# STM32F334R8T6-Module.net
KiCad netlist of a schematic drawn in Altium Designer
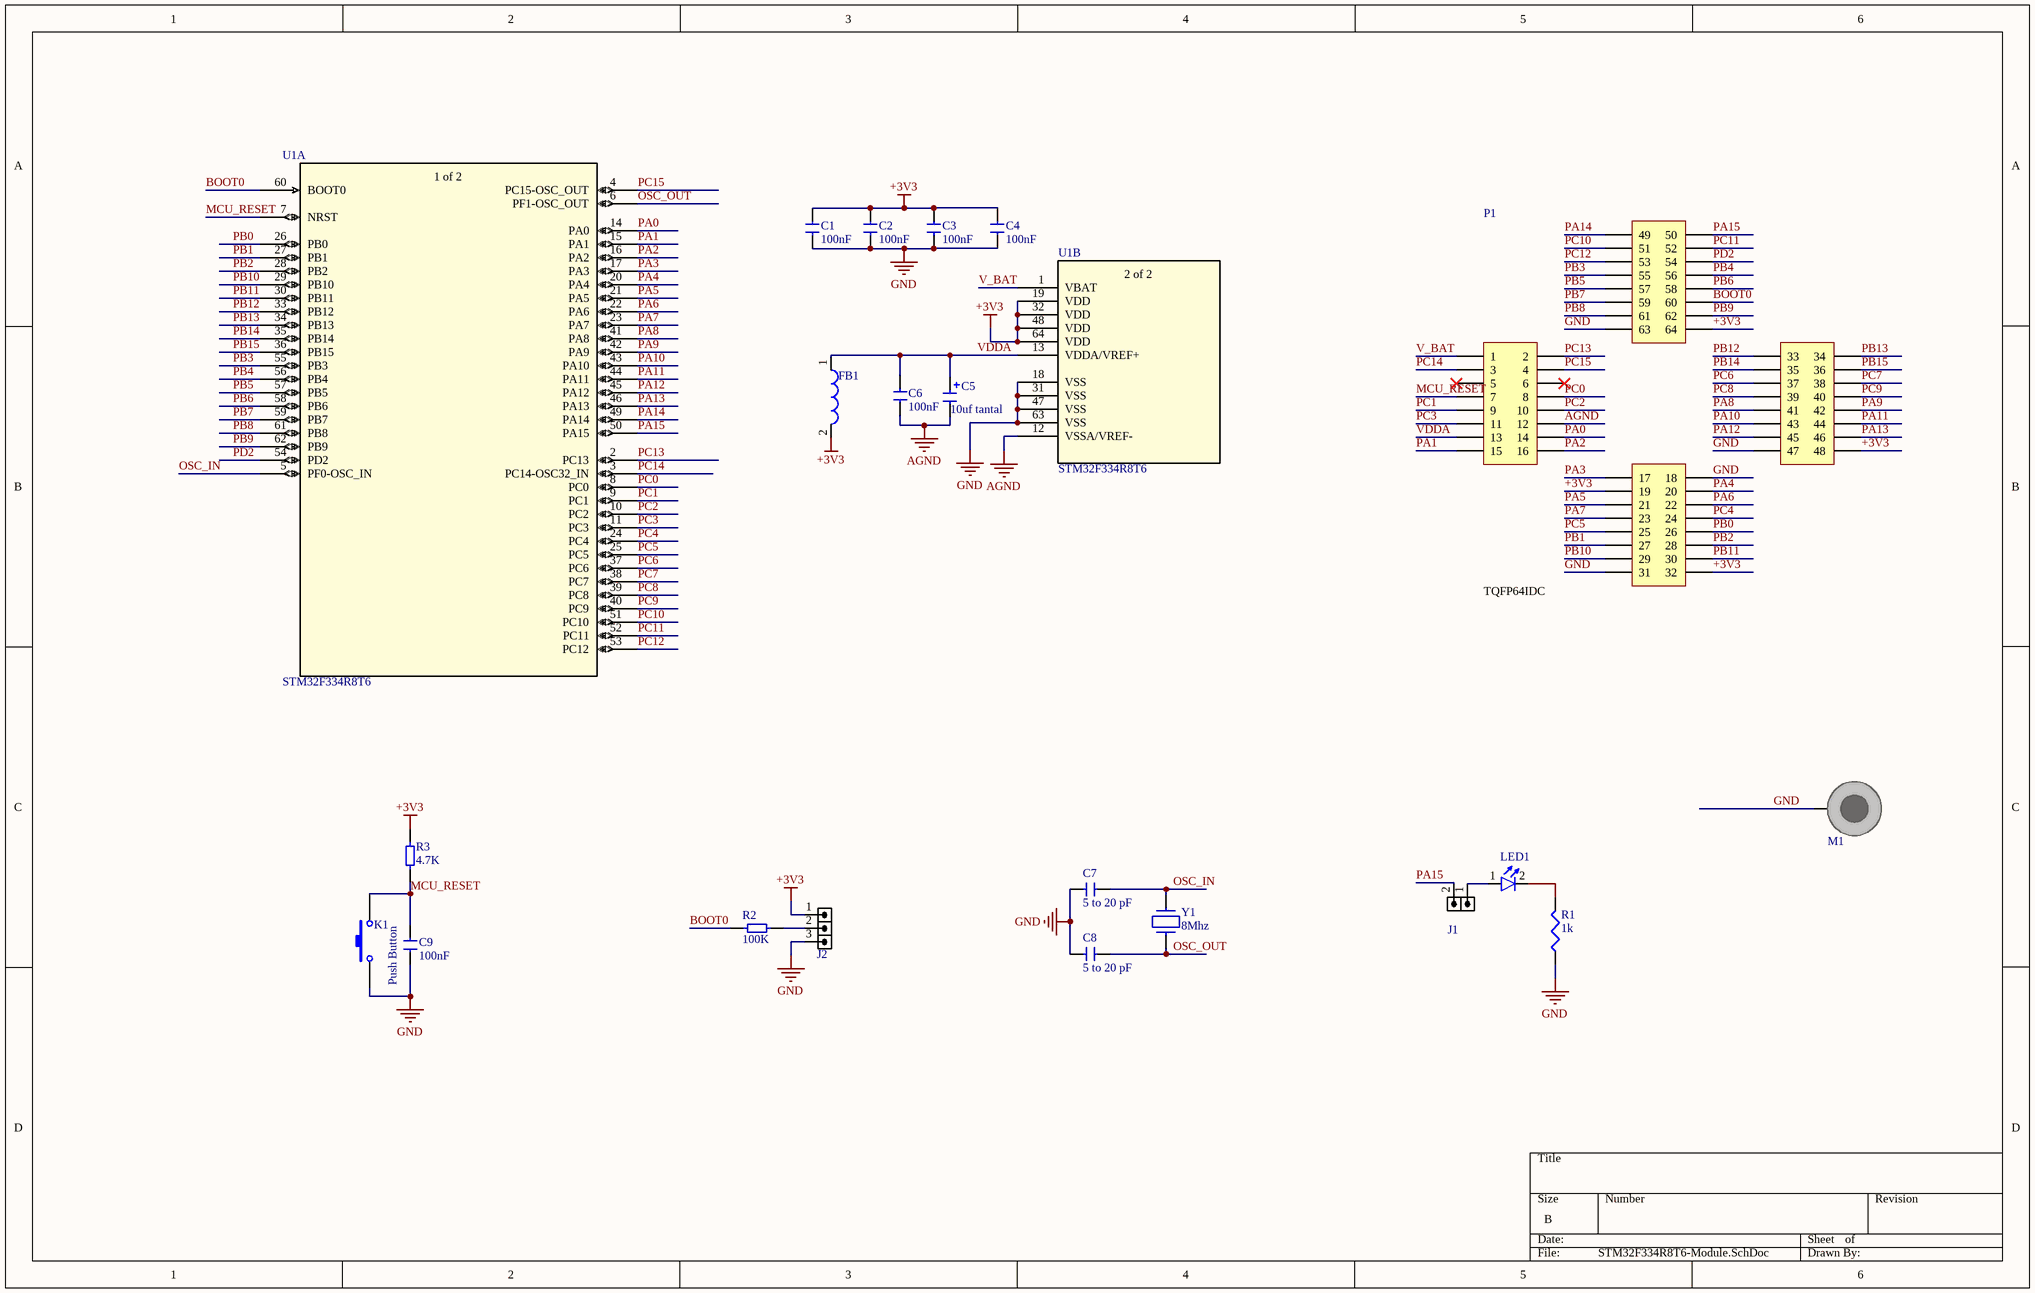
[diagram p0: STM32F334R8T6-Module.SchDoc]

(export (version "E")
  (design (tool "Eeschema 10.0.6"))
  (components
    (comp (ref "C1")
      (value "Comment")
      (footprint "CAP 1206 (3216X15L)")
      (fields (field (name "ALTIUM_UNNAMED_1") "100nF"))
      (libsource (lib "DotexGroup_LIB") (part "Capacitor SMD"))
    )
    (comp (ref "C2")
      (value "Comment")
      (footprint "CAP 1206 (3216X15L)")
      (fields (field (name "ALTIUM_UNNAMED_1") "100nF"))
      (libsource (lib "DotexGroup_LIB") (part "Capacitor SMD"))
    )
    (comp (ref "C3")
      (value "Comment")
      (footprint "CAP 1206 (3216X15L)")
      (fields (field (name "ALTIUM_UNNAMED_1") "100nF"))
      (libsource (lib "DotexGroup_LIB") (part "Capacitor SMD"))
    )
    (comp (ref "C4")
      (value "Comment")
      (footprint "CAP 1206 (3216X15L)")
      (fields (field (name "ALTIUM_UNNAMED_1") "100nF"))
      (libsource (lib "DotexGroup_LIB") (part "Capacitor SMD"))
    )
    (comp (ref "C5")
      (value "10uf tantal")
      (footprint "cap-e-2")
      (libsource (lib "DotexGroup_LIB") (part "Capacitor Tantalium"))
    )
    (comp (ref "C6")
      (value "Comment")
      (footprint "CAP 1206 (3216X15L)")
      (fields (field (name "ALTIUM_UNNAMED_1") "100nF"))
      (libsource (lib "DotexGroup_LIB") (part "Capacitor SMD"))
    )
    (comp (ref "C7")
      (value "Comment")
      (footprint "CAP 1206 (3216X15L)")
      (fields (field (name "ALTIUM_UNNAMED_1") "5 to 20 pF"))
      (libsource (lib "DotexGroup_LIB") (part "Capacitor SMD"))
    )
    (comp (ref "C8")
      (value "Comment")
      (footprint "CAP 1206 (3216X15L)")
      (fields (field (name "ALTIUM_UNNAMED_1") "5 to 20 pF"))
      (libsource (lib "DotexGroup_LIB") (part "Capacitor SMD"))
    )
    (comp (ref "C9")
      (value "Comment")
      (footprint "CAP 1206 (3216X15L)")
      (fields (field (name "ALTIUM_UNNAMED_1") "100nF"))
      (libsource (lib "DotexGroup_LIB") (part "Capacitor SMD"))
    )
    (comp (ref "FB1")
      (value "Comment")
      (footprint "INDC4532")
      (libsource (lib "DotexGroup_LIB") (part "Ferrit Bead"))
    )
    (comp (ref "J1")
      (value "HDRM2")
      (footprint "HDR1X2")
      (description "CONN, HEADER, Male, pitch: 2.54mm, 2POS")
      (libsource (lib "conn_header") (part "HDR_M_1X2"))
    )
    (comp (ref "J2")
      (value "HDRM3")
      (footprint "HDR1X3")
      (description "CONN, HEADER, Male, pitch: 2.54mm, 3POS")
      (libsource (lib "conn_header") (part "HDR_M_1X3"))
    )
    (comp (ref "K1")
      (value "Push Button")
      (footprint "SW PB SMD")
      (libsource (lib "DotexGroup_LIB") (part "Push Kay"))
    )
    (comp (ref "LED1")
      (value "HB")
      (footprint "LED SMD 1206")
      (description "LED")
      (fields (field (name "DESIGNER") "Saeid Jorablo"))
      (libsource (lib "3D") (part "LED"))
    )
    (comp (ref "M1")
      (value "Comment")
      (footprint "Stud-hole")
      (description "SCREW mouting, M1.6, 1.6mm diameter and 3.2mm PanHead")
      (libsource (lib "DotexGroup_LIB") (part "SCMH_M1P6"))
    )
    (comp (ref "P1")
      (value "TQFP64IDC")
      (footprint "tqfp64idc")
      (libsource (lib "Mylibrary2019") (part "TQFP64IDC"))
    )
    (comp (ref "R1") (value "1k") (footprint "RES 1206 (3216X08L)") (libsource (lib "*") (part "R")))
    (comp (ref "R2")
      (value "Comment")
      (footprint "RES 1206 (3216X08L)")
      (fields (field (name "ALTIUM_UNNAMED_1") "100K"))
      (libsource (lib "DotexGroup_LIB") (part "Resistor SMD"))
    )
    (comp (ref "R3")
      (value "Comment")
      (footprint "RES 1206 (3216X08L)")
      (fields (field (name "ALTIUM_UNNAMED_1") "4.7K"))
      (libsource (lib "DotexGroup_LIB") (part "Resistor SMD"))
    )
    (comp (ref "U1")
      (value "STM32F334R8T6")
      (footprint "STM32F334R8T6")
      (description "No Description Available")
      (fields (field (name "COPYRIGHT") "Copyright (C) 2023 Ultra Librarian. All rights reserved."))
      (libsource (lib "STM32F334R8T6") (part "STM32F334R8T6"))
    )
    (comp (ref "Y1")
      (value "8Mhz")
      (footprint "Crystal SMD")
      (libsource (lib "DotexGroup_LIB") (part "Xtal"))
    )
  )
  (nets
    (net (code "1") (name "+3V3") (class "Default")
      (node (ref "C1") (pin "2") (pintype "passive"))
      (node (ref "C2") (pin "2") (pintype "passive"))
      (node (ref "C3") (pin "2") (pintype "passive"))
      (node (ref "C4") (pin "2") (pintype "passive"))
      (node (ref "FB1") (pin "2") (pinfunction "2_2") (pintype "passive"))
      (node (ref "J2") (pin "1") (pinfunction "1_1") (pintype "passive"))
      (node (ref "P1") (pin "19") (pinfunction "19_19") (pintype "passive"))
      (node (ref "P1") (pin "32") (pinfunction "32_32") (pintype "passive"))
      (node (ref "P1") (pin "48") (pinfunction "48_48") (pintype "passive"))
      (node (ref "P1") (pin "64") (pinfunction "64_64") (pintype "passive"))
      (node (ref "R3") (pin "1") (pintype "passive"))
      (node (ref "U1") (pin "19") (pinfunction "VDD_19") (pintype "power_in"))
      (node (ref "U1") (pin "32") (pinfunction "VDD_32") (pintype "power_in"))
      (node (ref "U1") (pin "48") (pinfunction "VDD_48") (pintype "power_in"))
      (node (ref "U1") (pin "64") (pinfunction "VDD_64") (pintype "power_in"))
    )
    (net (code "2") (name "/BOOT0") (class "Default")
      (node (ref "P1") (pin "60") (pinfunction "60_60") (pintype "passive"))
      (node (ref "R2") (pin "1") (pintype "passive"))
      (node (ref "U1") (pin "60") (pinfunction "BOOT0_60") (pintype "input"))
    )
    (net (code "3") (name "/MCU_RESET") (class "Default")
      (node (ref "C9") (pin "1") (pintype "passive"))
      (node (ref "K1") (pin "2") (pinfunction "2_2") (pintype "passive"))
      (node (ref "P1") (pin "7") (pinfunction "7_7") (pintype "passive"))
      (node (ref "R3") (pin "2") (pintype "passive"))
      (node (ref "U1") (pin "7") (pinfunction "NRST_7") (pintype "bidirectional"))
    )
    (net (code "4") (name "/OSC_IN") (class "Default")
      (node (ref "C7") (pin "2") (pintype "passive"))
      (node (ref "U1") (pin "5") (pinfunction "PF0-OSC_IN_5") (pintype "bidirectional"))
      (node (ref "Y1") (pin "2") (pintype "passive"))
    )
    (net (code "5") (name "/OSC_OUT") (class "Default")
      (node (ref "C8") (pin "1") (pintype "passive"))
      (node (ref "U1") (pin "6") (pinfunction "PF1-OSC_OUT_6") (pintype "bidirectional"))
      (node (ref "Y1") (pin "1") (pintype "passive"))
    )
    (net (code "6") (name "/PA0") (class "Default")
      (node (ref "P1") (pin "14") (pinfunction "14_14") (pintype "passive"))
      (node (ref "U1") (pin "14") (pinfunction "PA0_14") (pintype "bidirectional"))
    )
    (net (code "7") (name "/PA1") (class "Default")
      (node (ref "P1") (pin "15") (pinfunction "15_15") (pintype "passive"))
      (node (ref "U1") (pin "15") (pinfunction "PA1_15") (pintype "bidirectional"))
    )
    (net (code "8") (name "/PA2") (class "Default")
      (node (ref "P1") (pin "16") (pinfunction "16_16") (pintype "passive"))
      (node (ref "U1") (pin "16") (pinfunction "PA2_16") (pintype "bidirectional"))
    )
    (net (code "9") (name "/PA3") (class "Default")
      (node (ref "P1") (pin "17") (pinfunction "17_17") (pintype "passive"))
      (node (ref "U1") (pin "17") (pinfunction "PA3_17") (pintype "bidirectional"))
    )
    (net (code "10") (name "/PA4") (class "Default")
      (node (ref "P1") (pin "20") (pinfunction "20_20") (pintype "passive"))
      (node (ref "U1") (pin "20") (pinfunction "PA4_20") (pintype "bidirectional"))
    )
    (net (code "11") (name "/PA5") (class "Default")
      (node (ref "P1") (pin "21") (pinfunction "21_21") (pintype "passive"))
      (node (ref "U1") (pin "21") (pinfunction "PA5_21") (pintype "bidirectional"))
    )
    (net (code "12") (name "/PA6") (class "Default")
      (node (ref "P1") (pin "22") (pinfunction "22_22") (pintype "passive"))
      (node (ref "U1") (pin "22") (pinfunction "PA6_22") (pintype "bidirectional"))
    )
    (net (code "13") (name "/PA7") (class "Default")
      (node (ref "P1") (pin "23") (pinfunction "23_23") (pintype "passive"))
      (node (ref "U1") (pin "23") (pinfunction "PA7_23") (pintype "bidirectional"))
    )
    (net (code "14") (name "/PA8") (class "Default")
      (node (ref "P1") (pin "41") (pinfunction "41_41") (pintype "passive"))
      (node (ref "U1") (pin "41") (pinfunction "PA8_41") (pintype "bidirectional"))
    )
    (net (code "15") (name "/PA9") (class "Default")
      (node (ref "P1") (pin "42") (pinfunction "42_42") (pintype "passive"))
      (node (ref "U1") (pin "42") (pinfunction "PA9_42") (pintype "bidirectional"))
    )
    (net (code "16") (name "/PA10") (class "Default")
      (node (ref "P1") (pin "43") (pinfunction "43_43") (pintype "passive"))
      (node (ref "U1") (pin "43") (pinfunction "PA10_43") (pintype "bidirectional"))
    )
    (net (code "17") (name "/PA11") (class "Default")
      (node (ref "P1") (pin "44") (pinfunction "44_44") (pintype "passive"))
      (node (ref "U1") (pin "44") (pinfunction "PA11_44") (pintype "bidirectional"))
    )
    (net (code "18") (name "/PA12") (class "Default")
      (node (ref "P1") (pin "45") (pinfunction "45_45") (pintype "passive"))
      (node (ref "U1") (pin "45") (pinfunction "PA12_45") (pintype "bidirectional"))
    )
    (net (code "19") (name "/PA13") (class "Default")
      (node (ref "P1") (pin "46") (pinfunction "46_46") (pintype "passive"))
      (node (ref "U1") (pin "46") (pinfunction "PA13_46") (pintype "bidirectional"))
    )
    (net (code "20") (name "/PA14") (class "Default")
      (node (ref "P1") (pin "49") (pinfunction "49_49") (pintype "passive"))
      (node (ref "U1") (pin "49") (pinfunction "PA14_49") (pintype "bidirectional"))
    )
    (net (code "21") (name "/PA15") (class "Default")
      (node (ref "J1") (pin "2") (pinfunction "2_2") (pintype "passive"))
      (node (ref "P1") (pin "50") (pinfunction "50_50") (pintype "passive"))
      (node (ref "U1") (pin "50") (pinfunction "PA15_50") (pintype "bidirectional"))
    )
    (net (code "22") (name "/PB0") (class "Default")
      (node (ref "P1") (pin "26") (pinfunction "26_26") (pintype "passive"))
      (node (ref "U1") (pin "26") (pinfunction "PB0_26") (pintype "bidirectional"))
    )
    (net (code "23") (name "/PB1") (class "Default")
      (node (ref "P1") (pin "27") (pinfunction "27_27") (pintype "passive"))
      (node (ref "U1") (pin "27") (pinfunction "PB1_27") (pintype "bidirectional"))
    )
    (net (code "24") (name "/PB2") (class "Default")
      (node (ref "P1") (pin "28") (pinfunction "28_28") (pintype "passive"))
      (node (ref "U1") (pin "28") (pinfunction "PB2_28") (pintype "bidirectional"))
    )
    (net (code "25") (name "/PB3") (class "Default")
      (node (ref "P1") (pin "55") (pinfunction "55_55") (pintype "passive"))
      (node (ref "U1") (pin "55") (pinfunction "PB3_55") (pintype "bidirectional"))
    )
    (net (code "26") (name "/PB4") (class "Default")
      (node (ref "P1") (pin "56") (pinfunction "56_56") (pintype "passive"))
      (node (ref "U1") (pin "56") (pinfunction "PB4_56") (pintype "bidirectional"))
    )
    (net (code "27") (name "/PB5") (class "Default")
      (node (ref "P1") (pin "57") (pinfunction "57_57") (pintype "passive"))
      (node (ref "U1") (pin "57") (pinfunction "PB5_57") (pintype "bidirectional"))
    )
    (net (code "28") (name "/PB6") (class "Default")
      (node (ref "P1") (pin "58") (pinfunction "58_58") (pintype "passive"))
      (node (ref "U1") (pin "58") (pinfunction "PB6_58") (pintype "bidirectional"))
    )
    (net (code "29") (name "/PB7") (class "Default")
      (node (ref "P1") (pin "59") (pinfunction "59_59") (pintype "passive"))
      (node (ref "U1") (pin "59") (pinfunction "PB7_59") (pintype "bidirectional"))
    )
    (net (code "30") (name "/PB8") (class "Default")
      (node (ref "P1") (pin "61") (pinfunction "61_61") (pintype "passive"))
      (node (ref "U1") (pin "61") (pinfunction "PB8_61") (pintype "bidirectional"))
    )
    (net (code "31") (name "/PB9") (class "Default")
      (node (ref "P1") (pin "62") (pinfunction "62_62") (pintype "passive"))
      (node (ref "U1") (pin "62") (pinfunction "PB9_62") (pintype "bidirectional"))
    )
    (net (code "32") (name "/PB10") (class "Default")
      (node (ref "P1") (pin "29") (pinfunction "29_29") (pintype "passive"))
      (node (ref "U1") (pin "29") (pinfunction "PB10_29") (pintype "bidirectional"))
    )
    (net (code "33") (name "/PB11") (class "Default")
      (node (ref "P1") (pin "30") (pinfunction "30_30") (pintype "passive"))
      (node (ref "U1") (pin "30") (pinfunction "PB11_30") (pintype "bidirectional"))
    )
    (net (code "34") (name "/PB12") (class "Default")
      (node (ref "P1") (pin "33") (pinfunction "33_33") (pintype "passive"))
      (node (ref "U1") (pin "33") (pinfunction "PB12_33") (pintype "bidirectional"))
    )
    (net (code "35") (name "/PB13") (class "Default")
      (node (ref "P1") (pin "34") (pinfunction "34_34") (pintype "passive"))
      (node (ref "U1") (pin "34") (pinfunction "PB13_34") (pintype "bidirectional"))
    )
    (net (code "36") (name "/PB14") (class "Default")
      (node (ref "P1") (pin "35") (pinfunction "35_35") (pintype "passive"))
      (node (ref "U1") (pin "35") (pinfunction "PB14_35") (pintype "bidirectional"))
    )
    (net (code "37") (name "/PB15") (class "Default")
      (node (ref "P1") (pin "36") (pinfunction "36_36") (pintype "passive"))
      (node (ref "U1") (pin "36") (pinfunction "PB15_36") (pintype "bidirectional"))
    )
    (net (code "38") (name "/PC0") (class "Default")
      (node (ref "P1") (pin "8") (pinfunction "8_8") (pintype "passive"))
      (node (ref "U1") (pin "8") (pinfunction "PC0_8") (pintype "bidirectional"))
    )
    (net (code "39") (name "/PC1") (class "Default")
      (node (ref "P1") (pin "9") (pinfunction "9_9") (pintype "passive"))
      (node (ref "U1") (pin "9") (pinfunction "PC1_9") (pintype "bidirectional"))
    )
    (net (code "40") (name "/PC2") (class "Default")
      (node (ref "P1") (pin "10") (pinfunction "10_10") (pintype "passive"))
      (node (ref "U1") (pin "10") (pinfunction "PC2_10") (pintype "bidirectional"))
    )
    (net (code "41") (name "/PC3") (class "Default")
      (node (ref "P1") (pin "11") (pinfunction "11_11") (pintype "passive"))
      (node (ref "U1") (pin "11") (pinfunction "PC3_11") (pintype "bidirectional"))
    )
    (net (code "42") (name "/PC4") (class "Default")
      (node (ref "P1") (pin "24") (pinfunction "24_24") (pintype "passive"))
      (node (ref "U1") (pin "24") (pinfunction "PC4_24") (pintype "bidirectional"))
    )
    (net (code "43") (name "/PC5") (class "Default")
      (node (ref "P1") (pin "25") (pinfunction "25_25") (pintype "passive"))
      (node (ref "U1") (pin "25") (pinfunction "PC5_25") (pintype "bidirectional"))
    )
    (net (code "44") (name "/PC6") (class "Default")
      (node (ref "P1") (pin "37") (pinfunction "37_37") (pintype "passive"))
      (node (ref "U1") (pin "37") (pinfunction "PC6_37") (pintype "bidirectional"))
    )
    (net (code "45") (name "/PC7") (class "Default")
      (node (ref "P1") (pin "38") (pinfunction "38_38") (pintype "passive"))
      (node (ref "U1") (pin "38") (pinfunction "PC7_38") (pintype "bidirectional"))
    )
    (net (code "46") (name "/PC8") (class "Default")
      (node (ref "P1") (pin "39") (pinfunction "39_39") (pintype "passive"))
      (node (ref "U1") (pin "39") (pinfunction "PC8_39") (pintype "bidirectional"))
    )
    (net (code "47") (name "/PC9") (class "Default")
      (node (ref "P1") (pin "40") (pinfunction "40_40") (pintype "passive"))
      (node (ref "U1") (pin "40") (pinfunction "PC9_40") (pintype "bidirectional"))
    )
    (net (code "48") (name "/PC10") (class "Default")
      (node (ref "P1") (pin "51") (pinfunction "51_51") (pintype "passive"))
      (node (ref "U1") (pin "51") (pinfunction "PC10_51") (pintype "bidirectional"))
    )
    (net (code "49") (name "/PC11") (class "Default")
      (node (ref "P1") (pin "52") (pinfunction "52_52") (pintype "passive"))
      (node (ref "U1") (pin "52") (pinfunction "PC11_52") (pintype "bidirectional"))
    )
    (net (code "50") (name "/PC12") (class "Default")
      (node (ref "P1") (pin "53") (pinfunction "53_53") (pintype "passive"))
      (node (ref "U1") (pin "53") (pinfunction "PC12_53") (pintype "bidirectional"))
    )
    (net (code "51") (name "/PC13") (class "Default")
      (node (ref "P1") (pin "2") (pinfunction "2_2") (pintype "passive"))
      (node (ref "U1") (pin "2") (pinfunction "PC13_2") (pintype "bidirectional"))
    )
    (net (code "52") (name "/PC14") (class "Default")
      (node (ref "P1") (pin "3") (pinfunction "3_3") (pintype "passive"))
      (node (ref "U1") (pin "3") (pinfunction "PC14-OSC32_IN_3") (pintype "bidirectional"))
    )
    (net (code "53") (name "/PC15") (class "Default")
      (node (ref "P1") (pin "4") (pinfunction "4_4") (pintype "passive"))
      (node (ref "U1") (pin "4") (pinfunction "PC15-OSC_OUT_4") (pintype "bidirectional"))
    )
    (net (code "54") (name "/PD2") (class "Default")
      (node (ref "P1") (pin "54") (pinfunction "54_54") (pintype "passive"))
      (node (ref "U1") (pin "54") (pinfunction "PD2_54") (pintype "bidirectional"))
    )
    (net (code "55") (name "/VDDA") (class "Default")
      (node (ref "C5") (pin "1") (pintype "passive"))
      (node (ref "C6") (pin "2") (pintype "passive"))
      (node (ref "FB1") (pin "1") (pinfunction "1_1") (pintype "passive"))
      (node (ref "P1") (pin "13") (pinfunction "13_13") (pintype "passive"))
      (node (ref "U1") (pin "13") (pinfunction "VDDA/VREF+_13") (pintype "power_in"))
    )
    (net (code "56") (name "/V_BAT") (class "Default")
      (node (ref "P1") (pin "1") (pinfunction "1_1") (pintype "passive"))
      (node (ref "U1") (pin "1") (pinfunction "VBAT_1") (pintype "power_in"))
    )
    (net (code "57") (name "AGND") (class "Default")
      (node (ref "C5") (pin "2") (pintype "passive"))
      (node (ref "C6") (pin "1") (pintype "passive"))
      (node (ref "P1") (pin "12") (pinfunction "12_12") (pintype "passive"))
      (node (ref "U1") (pin "12") (pinfunction "VSSA/VREF-_12") (pintype "power_in"))
    )
    (net (code "58") (name "GND") (class "Default")
      (node (ref "C1") (pin "1") (pintype "passive"))
      (node (ref "C2") (pin "1") (pintype "passive"))
      (node (ref "C3") (pin "1") (pintype "passive"))
      (node (ref "C4") (pin "1") (pintype "passive"))
      (node (ref "C7") (pin "1") (pintype "passive"))
      (node (ref "C8") (pin "2") (pintype "passive"))
      (node (ref "C9") (pin "2") (pintype "passive"))
      (node (ref "J2") (pin "3") (pinfunction "3_3") (pintype "passive"))
      (node (ref "K1") (pin "1") (pinfunction "1_1") (pintype "passive"))
      (node (ref "M1") (pin "1") (pinfunction "1_1") (pintype "passive"))
      (node (ref "P1") (pin "18") (pinfunction "18_18") (pintype "passive"))
      (node (ref "P1") (pin "31") (pinfunction "31_31") (pintype "passive"))
      (node (ref "P1") (pin "47") (pinfunction "47_47") (pintype "passive"))
      (node (ref "P1") (pin "63") (pinfunction "63_63") (pintype "passive"))
      (node (ref "R1") (pin "1") (pintype "passive"))
      (node (ref "U1") (pin "18") (pinfunction "VSS_18") (pintype "power_in"))
      (node (ref "U1") (pin "31") (pinfunction "VSS_31") (pintype "power_in"))
      (node (ref "U1") (pin "47") (pinfunction "VSS_47") (pintype "power_in"))
      (node (ref "U1") (pin "63") (pinfunction "VSS_63") (pintype "power_in"))
    )
    (net (code "59") (name "Net-(J2-Pad2)") (class "Default")
      (node (ref "J2") (pin "2") (pinfunction "2_2") (pintype "passive"))
      (node (ref "R2") (pin "2") (pintype "passive"))
    )
    (net (code "60") (name "Net-(LED1-A)") (class "Default")
      (node (ref "J1") (pin "1") (pinfunction "1_1") (pintype "passive"))
      (node (ref "LED1") (pin "1") (pinfunction "A_1") (pintype "passive"))
    )
    (net (code "61") (name "Net-(LED1-K)") (class "Default")
      (node (ref "LED1") (pin "2") (pinfunction "K_2") (pintype "passive"))
      (node (ref "R1") (pin "2") (pintype "passive"))
    )
    (net (code "62") (name "unconnected-(P1-Pad5)") (class "Default")
      (node (ref "P1") (pin "5") (pinfunction "5_5") (pintype "passive+no_connect"))
    )
    (net (code "63") (name "unconnected-(P1-Pad6)") (class "Default")
      (node (ref "P1") (pin "6") (pinfunction "6_6") (pintype "passive+no_connect"))
    )
  )
)
